# AD620_stopband.net
KiCad netlist of a schematic drawn in EAGLE
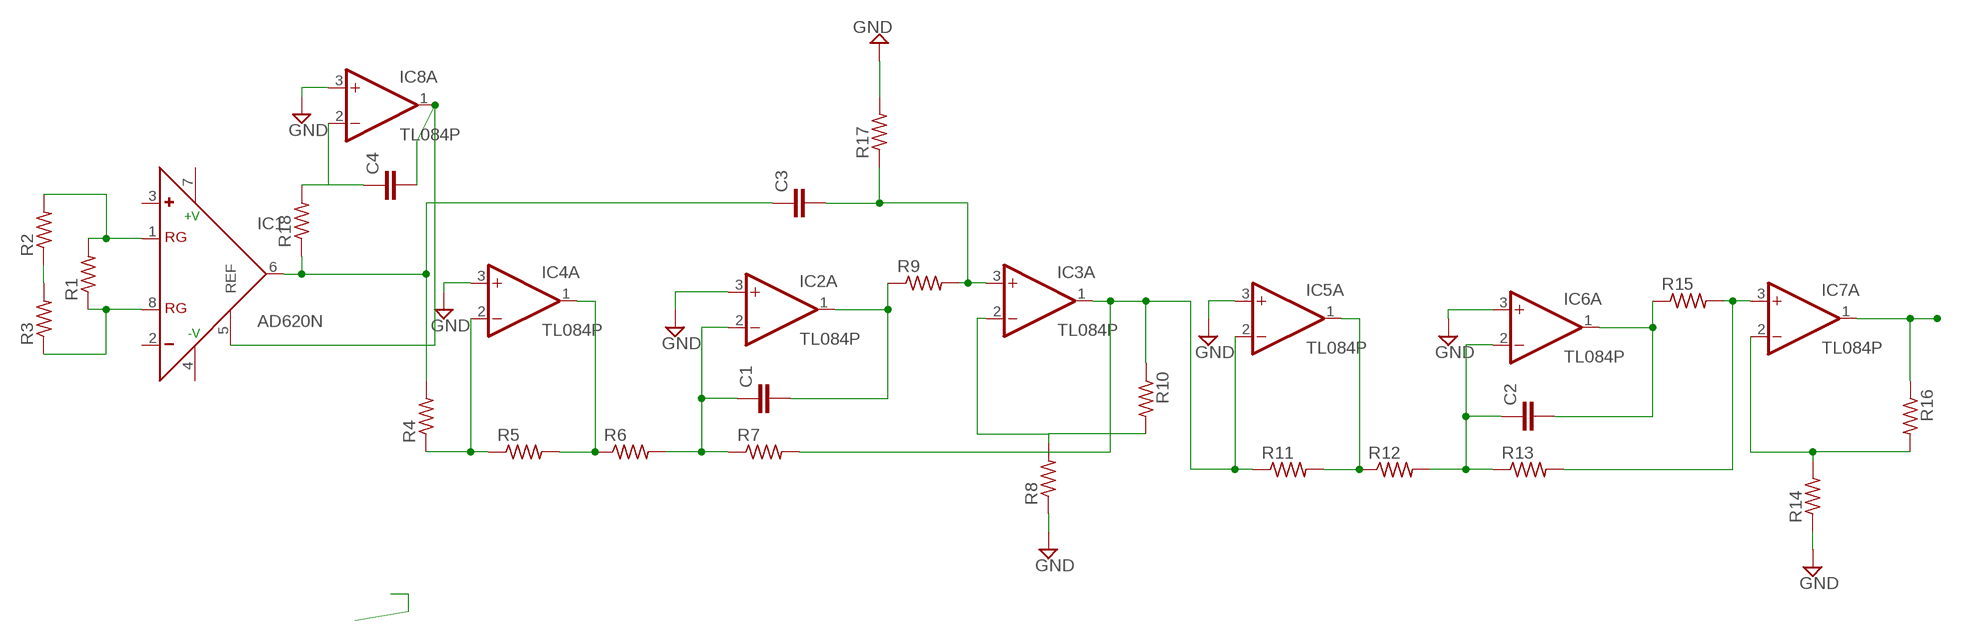
[diagram p0: schematic, sheet 1]

(export (version "E")
  (design (tool "Eeschema 10.0.6"))
  (components
    (comp (ref "C1")
      (value "C-EU050-030X075")
      (footprint "eagle-import:C050-030X075")
      (libsource (lib "eagle-import") (part "C-EU050-030X075"))
    )
    (comp (ref "C2")
      (value "C-EU050-030X075")
      (footprint "eagle-import:C050-030X075")
      (libsource (lib "eagle-import") (part "C-EU050-030X075"))
    )
    (comp (ref "C3")
      (value "C-EU050-030X075")
      (footprint "eagle-import:C050-030X075")
      (libsource (lib "eagle-import") (part "C-EU050-030X075"))
    )
    (comp (ref "C4")
      (value "C-EU050-030X075")
      (footprint "eagle-import:C050-030X075")
      (libsource (lib "eagle-import") (part "C-EU050-030X075"))
    )
    (comp (ref "IC1")
      (value "AD620N")
      (footprint "eagle-import:DIL08")
      (fields (field (name "MF") "ALTERA CORPORATION") (field (name "MPN") "AD620AN"))
      (libsource (lib "eagle-import") (part "AD620N"))
    )
    (comp (ref "IC2")
      (value "TL084P")
      (footprint "eagle-import:DIL14")
      (libsource (lib "eagle-import") (part "TL084P"))
    )
    (comp (ref "IC3")
      (value "TL084P")
      (footprint "eagle-import:DIL14")
      (libsource (lib "eagle-import") (part "TL084P"))
    )
    (comp (ref "IC4")
      (value "TL084P")
      (footprint "eagle-import:DIL14")
      (libsource (lib "eagle-import") (part "TL084P"))
    )
    (comp (ref "IC5")
      (value "TL084P")
      (footprint "eagle-import:DIL14")
      (libsource (lib "eagle-import") (part "TL084P"))
    )
    (comp (ref "IC6")
      (value "TL084P")
      (footprint "eagle-import:DIL14")
      (libsource (lib "eagle-import") (part "TL084P"))
    )
    (comp (ref "IC7")
      (value "TL084P")
      (footprint "eagle-import:DIL14")
      (libsource (lib "eagle-import") (part "TL084P"))
    )
    (comp (ref "IC8")
      (value "TL084P")
      (footprint "eagle-import:DIL14")
      (libsource (lib "eagle-import") (part "TL084P"))
    )
    (comp (ref "R1")
      (value "R-US_0204/5")
      (footprint "eagle-import:0204_5")
      (libsource (lib "eagle-import") (part "R-US_0204/5"))
    )
    (comp (ref "R2")
      (value "R-US_0204/5")
      (footprint "eagle-import:0204_5")
      (libsource (lib "eagle-import") (part "R-US_0204/5"))
    )
    (comp (ref "R3")
      (value "R-US_0204/5")
      (footprint "eagle-import:0204_5")
      (libsource (lib "eagle-import") (part "R-US_0204/5"))
    )
    (comp (ref "R4")
      (value "R-US_0204/5")
      (footprint "eagle-import:0204_5")
      (libsource (lib "eagle-import") (part "R-US_0204/5"))
    )
    (comp (ref "R5")
      (value "R-US_0204/5")
      (footprint "eagle-import:0204_5")
      (libsource (lib "eagle-import") (part "R-US_0204/5"))
    )
    (comp (ref "R6")
      (value "R-US_0204/5")
      (footprint "eagle-import:0204_5")
      (libsource (lib "eagle-import") (part "R-US_0204/5"))
    )
    (comp (ref "R7")
      (value "R-US_0204/5")
      (footprint "eagle-import:0204_5")
      (libsource (lib "eagle-import") (part "R-US_0204/5"))
    )
    (comp (ref "R8")
      (value "R-US_0204/5")
      (footprint "eagle-import:0204_5")
      (libsource (lib "eagle-import") (part "R-US_0204/5"))
    )
    (comp (ref "R9")
      (value "R-US_0204/5")
      (footprint "eagle-import:0204_5")
      (libsource (lib "eagle-import") (part "R-US_0204/5"))
    )
    (comp (ref "R10")
      (value "R-US_0204/5")
      (footprint "eagle-import:0204_5")
      (libsource (lib "eagle-import") (part "R-US_0204/5"))
    )
    (comp (ref "R11")
      (value "R-US_0204/5")
      (footprint "eagle-import:0204_5")
      (libsource (lib "eagle-import") (part "R-US_0204/5"))
    )
    (comp (ref "R12")
      (value "R-US_0204/5")
      (footprint "eagle-import:0204_5")
      (libsource (lib "eagle-import") (part "R-US_0204/5"))
    )
    (comp (ref "R13")
      (value "R-US_0204/5")
      (footprint "eagle-import:0204_5")
      (libsource (lib "eagle-import") (part "R-US_0204/5"))
    )
    (comp (ref "R14")
      (value "R-US_0204/5")
      (footprint "eagle-import:0204_5")
      (libsource (lib "eagle-import") (part "R-US_0204/5"))
    )
    (comp (ref "R15")
      (value "R-US_0204/5")
      (footprint "eagle-import:0204_5")
      (libsource (lib "eagle-import") (part "R-US_0204/5"))
    )
    (comp (ref "R16")
      (value "R-US_0204/5")
      (footprint "eagle-import:0204_5")
      (libsource (lib "eagle-import") (part "R-US_0204/5"))
    )
    (comp (ref "R17")
      (value "R-US_0204/5")
      (footprint "eagle-import:0204_5")
      (libsource (lib "eagle-import") (part "R-US_0204/5"))
    )
    (comp (ref "R18")
      (value "R-US_0204/5")
      (footprint "eagle-import:0204_5")
      (libsource (lib "eagle-import") (part "R-US_0204/5"))
    )
  )
  (nets
    (net (code "1") (name "/+V") (class "Default")
      (node (ref "IC1") (pin "7") (pinfunction "+V_7") (pintype "power_in"))
    )
    (net (code "2") (name "/-V") (class "Default")
      (node (ref "IC1") (pin "4") (pinfunction "-V_4") (pintype "power_in"))
    )
    (net (code "3") (name "GND") (class "Default")
      (node (ref "IC2") (pin "3") (pinfunction "+IN_3") (pintype "input"))
      (node (ref "IC4") (pin "3") (pinfunction "+IN_3") (pintype "input"))
      (node (ref "IC5") (pin "3") (pinfunction "+IN_3") (pintype "input"))
      (node (ref "IC6") (pin "3") (pinfunction "+IN_3") (pintype "input"))
      (node (ref "IC8") (pin "3") (pinfunction "+IN_3") (pintype "input"))
      (node (ref "R14") (pin "1") (pinfunction "1_1") (pintype "passive"))
      (node (ref "R17") (pin "2") (pinfunction "2_2") (pintype "passive"))
      (node (ref "R8") (pin "1") (pinfunction "1_1") (pintype "passive"))
    )
    (net (code "4") (name "Net-(IC1-OUT)") (class "Default")
      (node (ref "C3") (pin "1") (pinfunction "1_1") (pintype "passive"))
      (node (ref "IC1") (pin "6") (pinfunction "OUT_6") (pintype "output"))
      (node (ref "R18") (pin "1") (pinfunction "1_1") (pintype "passive"))
      (node (ref "R4") (pin "2") (pinfunction "2_2") (pintype "passive"))
    )
    (net (code "5") (name "Net-(IC1-REF)") (class "Default")
      (node (ref "C4") (pin "2") (pinfunction "2_2") (pintype "passive"))
      (node (ref "IC1") (pin "5") (pinfunction "REF_5") (pintype "passive"))
      (node (ref "IC8") (pin "1") (pinfunction "OUT_1") (pintype "output"))
    )
    (net (code "6") (name "Net-(IC1-RG-Pad1)") (class "Default")
      (node (ref "IC1") (pin "1") (pinfunction "RG_1") (pintype "passive"))
      (node (ref "R1") (pin "2") (pinfunction "2_2") (pintype "passive"))
      (node (ref "R2") (pin "2") (pinfunction "2_2") (pintype "passive"))
    )
    (net (code "7") (name "Net-(IC1-RG-Pad8)") (class "Default")
      (node (ref "IC1") (pin "8") (pinfunction "RG_8") (pintype "passive"))
      (node (ref "R1") (pin "1") (pinfunction "1_1") (pintype "passive"))
      (node (ref "R3") (pin "1") (pinfunction "1_1") (pintype "passive"))
    )
    (net (code "8") (name "Net-(IC2A--IN)") (class "Default")
      (node (ref "C1") (pin "1") (pinfunction "1_1") (pintype "passive"))
      (node (ref "IC2") (pin "2") (pinfunction "-IN_2") (pintype "input"))
      (node (ref "R6") (pin "2") (pinfunction "2_2") (pintype "passive"))
      (node (ref "R7") (pin "1") (pinfunction "1_1") (pintype "passive"))
    )
    (net (code "9") (name "Net-(IC2A-OUT)") (class "Default")
      (node (ref "C1") (pin "2") (pinfunction "2_2") (pintype "passive"))
      (node (ref "IC2") (pin "1") (pinfunction "OUT_1") (pintype "output"))
      (node (ref "R9") (pin "1") (pinfunction "1_1") (pintype "passive"))
    )
    (net (code "10") (name "Net-(IC3A-+IN)") (class "Default")
      (node (ref "C3") (pin "2") (pinfunction "2_2") (pintype "passive"))
      (node (ref "IC3") (pin "3") (pinfunction "+IN_3") (pintype "input"))
      (node (ref "R17") (pin "1") (pinfunction "1_1") (pintype "passive"))
      (node (ref "R9") (pin "2") (pinfunction "2_2") (pintype "passive"))
    )
    (net (code "11") (name "Net-(IC3A--IN)") (class "Default")
      (node (ref "IC3") (pin "2") (pinfunction "-IN_2") (pintype "input"))
      (node (ref "R10") (pin "2") (pinfunction "2_2") (pintype "passive"))
      (node (ref "R8") (pin "2") (pinfunction "2_2") (pintype "passive"))
    )
    (net (code "12") (name "Net-(IC3A-OUT)") (class "Default")
      (node (ref "IC3") (pin "1") (pinfunction "OUT_1") (pintype "output"))
      (node (ref "IC5") (pin "2") (pinfunction "-IN_2") (pintype "input"))
      (node (ref "R10") (pin "1") (pinfunction "1_1") (pintype "passive"))
      (node (ref "R11") (pin "1") (pinfunction "1_1") (pintype "passive"))
      (node (ref "R7") (pin "2") (pinfunction "2_2") (pintype "passive"))
    )
    (net (code "13") (name "Net-(IC4A--IN)") (class "Default")
      (node (ref "IC4") (pin "2") (pinfunction "-IN_2") (pintype "input"))
      (node (ref "R4") (pin "1") (pinfunction "1_1") (pintype "passive"))
      (node (ref "R5") (pin "1") (pinfunction "1_1") (pintype "passive"))
    )
    (net (code "14") (name "Net-(IC4A-OUT)") (class "Default")
      (node (ref "IC4") (pin "1") (pinfunction "OUT_1") (pintype "output"))
      (node (ref "R5") (pin "2") (pinfunction "2_2") (pintype "passive"))
      (node (ref "R6") (pin "1") (pinfunction "1_1") (pintype "passive"))
    )
    (net (code "15") (name "Net-(IC5A-OUT)") (class "Default")
      (node (ref "IC5") (pin "1") (pinfunction "OUT_1") (pintype "output"))
      (node (ref "R11") (pin "2") (pinfunction "2_2") (pintype "passive"))
      (node (ref "R12") (pin "1") (pinfunction "1_1") (pintype "passive"))
    )
    (net (code "16") (name "Net-(IC6A--IN)") (class "Default")
      (node (ref "C2") (pin "1") (pinfunction "1_1") (pintype "passive"))
      (node (ref "IC6") (pin "2") (pinfunction "-IN_2") (pintype "input"))
      (node (ref "R12") (pin "2") (pinfunction "2_2") (pintype "passive"))
      (node (ref "R13") (pin "1") (pinfunction "1_1") (pintype "passive"))
    )
    (net (code "17") (name "Net-(IC6A-OUT)") (class "Default")
      (node (ref "C2") (pin "2") (pinfunction "2_2") (pintype "passive"))
      (node (ref "IC6") (pin "1") (pinfunction "OUT_1") (pintype "output"))
      (node (ref "R15") (pin "1") (pinfunction "1_1") (pintype "passive"))
    )
    (net (code "18") (name "Net-(IC7A-+IN)") (class "Default")
      (node (ref "IC7") (pin "3") (pinfunction "+IN_3") (pintype "input"))
      (node (ref "R13") (pin "2") (pinfunction "2_2") (pintype "passive"))
      (node (ref "R15") (pin "2") (pinfunction "2_2") (pintype "passive"))
    )
    (net (code "19") (name "Net-(IC7A--IN)") (class "Default")
      (node (ref "IC7") (pin "2") (pinfunction "-IN_2") (pintype "input"))
      (node (ref "R14") (pin "2") (pinfunction "2_2") (pintype "passive"))
      (node (ref "R16") (pin "2") (pinfunction "2_2") (pintype "passive"))
    )
    (net (code "20") (name "Net-(IC7A-OUT)") (class "Default")
      (node (ref "IC7") (pin "1") (pinfunction "OUT_1") (pintype "output"))
      (node (ref "R16") (pin "1") (pinfunction "1_1") (pintype "passive"))
    )
    (net (code "21") (name "Net-(IC8A--IN)") (class "Default")
      (node (ref "C4") (pin "1") (pinfunction "1_1") (pintype "passive"))
      (node (ref "IC8") (pin "2") (pinfunction "-IN_2") (pintype "input"))
      (node (ref "R18") (pin "2") (pinfunction "2_2") (pintype "passive"))
    )
    (net (code "22") (name "Net-(R2-Pad1)") (class "Default")
      (node (ref "R2") (pin "1") (pinfunction "1_1") (pintype "passive"))
      (node (ref "R3") (pin "2") (pinfunction "2_2") (pintype "passive"))
    )
    (net (code "23") (name "unconnected-(IC1-+-Pad3)") (class "Default")
      (node (ref "IC1") (pin "3") (pinfunction "+_3") (pintype "input"))
    )
    (net (code "24") (name "unconnected-(IC1---Pad2)") (class "Default")
      (node (ref "IC1") (pin "2") (pinfunction "-_2") (pintype "input"))
    )
  )
)
